# RJ45_Sheet.net
KiCad netlist of a schematic drawn in Altium Designer
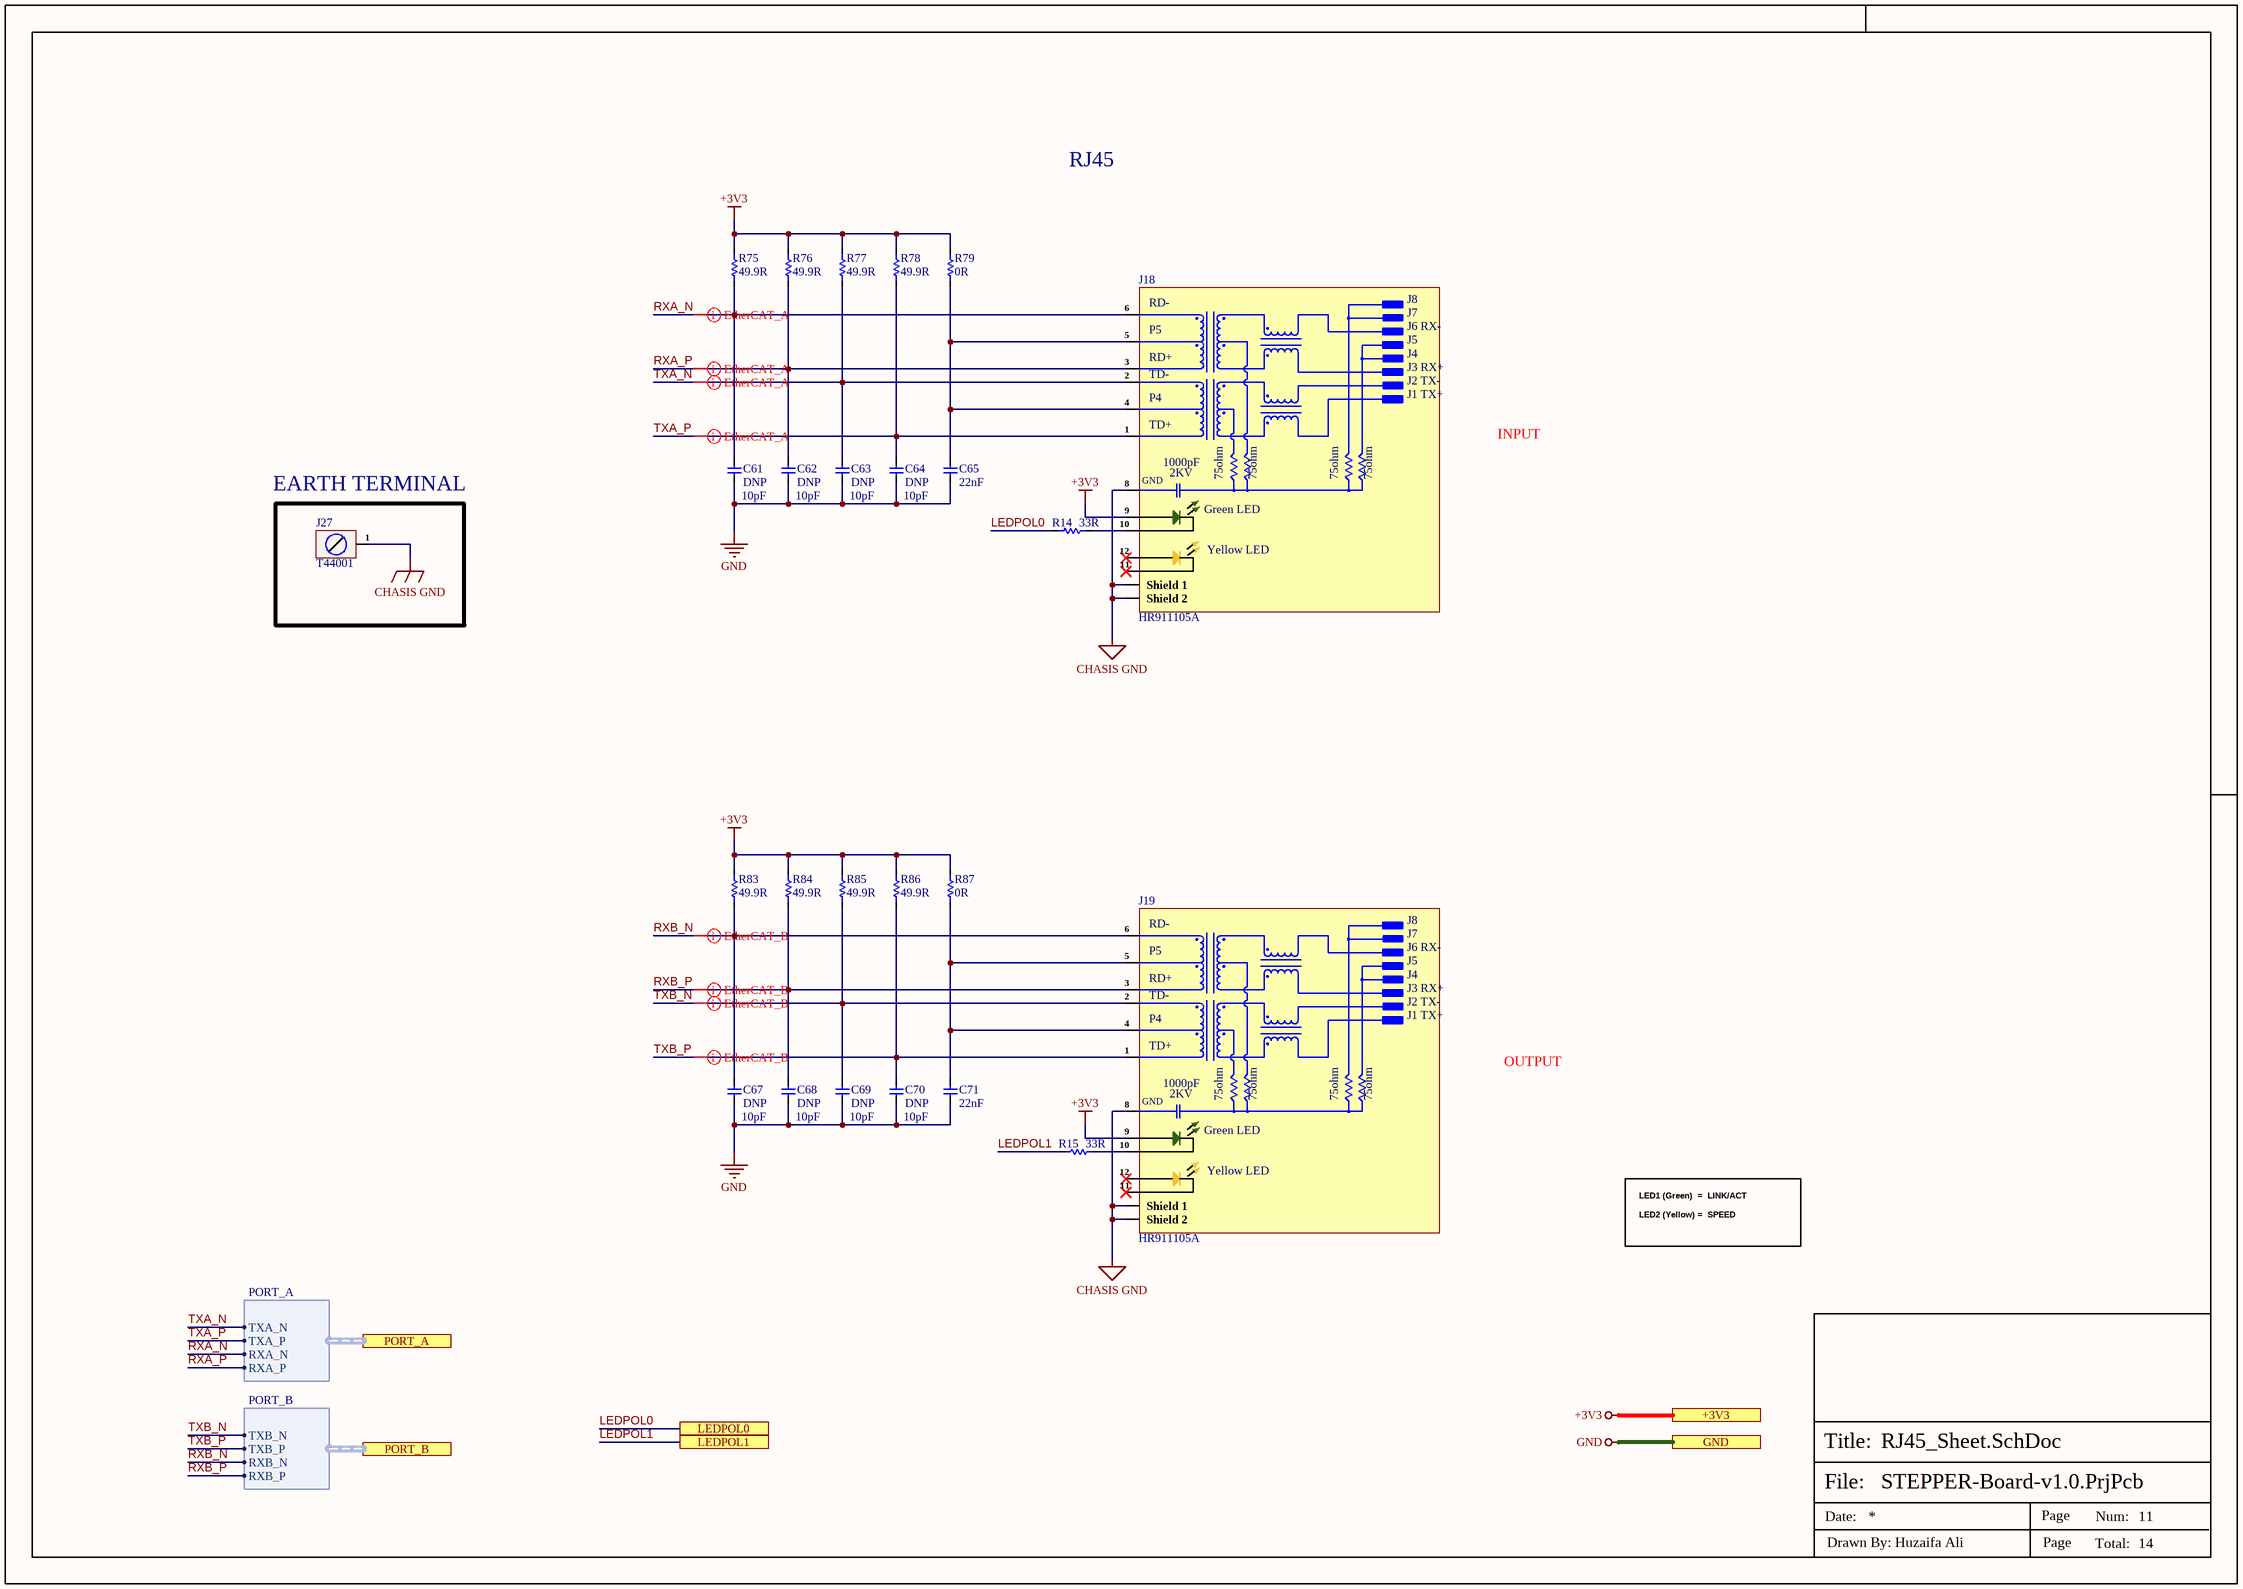
[diagram p0: RJ45_Sheet.SchDoc]

(export (version "E")
  (design (tool "Eeschema 10.0.6"))
  (components
    (comp (ref "C61")
      (value "DNP")
      (footprint "Cap-0402")
      (description "CAP CER 10PF 50V C0G/NP0 0402")
      (fields
        (field (name "MANUFACTURER") "Murata")
        (field (name "MANUFACTURER PART NUMBER") "GRM1555C1H100JA01D")
      )
      (libsource (lib "eSpark Libraries") (part "GRM1555C1H100JA01D"))
    )
    (comp (ref "C62")
      (value "DNP")
      (footprint "Cap-0402")
      (description "CAP CER 10PF 50V C0G/NP0 0402")
      (fields
        (field (name "MANUFACTURER") "Murata")
        (field (name "MANUFACTURER PART NUMBER") "GRM1555C1H100JA01D")
      )
      (libsource (lib "eSpark Libraries") (part "GRM1555C1H100JA01D"))
    )
    (comp (ref "C63")
      (value "DNP")
      (footprint "Cap-0402")
      (description "CAP CER 10PF 50V C0G/NP0 0402")
      (fields
        (field (name "MANUFACTURER") "Murata")
        (field (name "MANUFACTURER PART NUMBER") "GRM1555C1H100JA01D")
      )
      (libsource (lib "eSpark Libraries") (part "GRM1555C1H100JA01D"))
    )
    (comp (ref "C64")
      (value "DNP")
      (footprint "Cap-0402")
      (description "CAP CER 10PF 50V C0G/NP0 0402")
      (fields
        (field (name "MANUFACTURER") "Murata")
        (field (name "MANUFACTURER PART NUMBER") "GRM1555C1H100JA01D")
      )
      (libsource (lib "eSpark Libraries") (part "GRM1555C1H100JA01D"))
    )
    (comp (ref "C65")
      (value "22nF")
      (footprint "Cap-0402")
      (description "CAP CER 0.022UF 16V X7R 0402")
      (fields
        (field (name "MANUFACTURER") "Yageo")
        (field (name "MANUFACTURER PART NUMBER") "CC0402JRX7R7BB223")
      )
      (libsource (lib "eSpark Libraries") (part "CC0402JRX7R7BB223"))
    )
    (comp (ref "C67")
      (value "DNP")
      (footprint "Cap-0402")
      (description "CAP CER 10PF 50V C0G/NP0 0402")
      (fields
        (field (name "MANUFACTURER") "Murata")
        (field (name "MANUFACTURER PART NUMBER") "GRM1555C1H100JA01D")
      )
      (libsource (lib "eSpark Libraries") (part "GRM1555C1H100JA01D"))
    )
    (comp (ref "C68")
      (value "DNP")
      (footprint "Cap-0402")
      (description "CAP CER 10PF 50V C0G/NP0 0402")
      (fields
        (field (name "MANUFACTURER") "Murata")
        (field (name "MANUFACTURER PART NUMBER") "GRM1555C1H100JA01D")
      )
      (libsource (lib "eSpark Libraries") (part "GRM1555C1H100JA01D"))
    )
    (comp (ref "C69")
      (value "DNP")
      (footprint "Cap-0402")
      (description "CAP CER 10PF 50V C0G/NP0 0402")
      (fields
        (field (name "MANUFACTURER") "Murata")
        (field (name "MANUFACTURER PART NUMBER") "GRM1555C1H100JA01D")
      )
      (libsource (lib "eSpark Libraries") (part "GRM1555C1H100JA01D"))
    )
    (comp (ref "C70")
      (value "DNP")
      (footprint "Cap-0402")
      (description "CAP CER 10PF 50V C0G/NP0 0402")
      (fields
        (field (name "MANUFACTURER") "Murata")
        (field (name "MANUFACTURER PART NUMBER") "GRM1555C1H100JA01D")
      )
      (libsource (lib "eSpark Libraries") (part "GRM1555C1H100JA01D"))
    )
    (comp (ref "C71")
      (value "22nF")
      (footprint "Cap-0402")
      (description "CAP CER 0.022UF 16V X7R 0402")
      (fields
        (field (name "MANUFACTURER") "Yageo")
        (field (name "MANUFACTURER PART NUMBER") "CC0402JRX7R7BB223")
      )
      (libsource (lib "eSpark Libraries") (part "CC0402JRX7R7BB223"))
    )
    (comp (ref "J18")
      (value "HR911105A")
      (footprint "HR911105A")
      (description "RJ45 RJReceptacle 1 WithLED Plugin Ethernet Connectors/Modular Connectors (RJ45 RJ11) ROHS")
      (fields (field (name "MANUFACTURER") "HANRUN") (field (name "LCSC PART NUMBER") "C12074"))
      (libsource (lib "eSpark Libraries") (part "HR911105A"))
    )
    (comp (ref "J19")
      (value "HR911105A")
      (footprint "HR911105A")
      (description "RJ45 RJReceptacle 1 WithLED Plugin Ethernet Connectors/Modular Connectors (RJ45 RJ11) ROHS")
      (fields (field (name "MANUFACTURER") "HANRUN") (field (name "LCSC PART NUMBER") "C12074"))
      (libsource (lib "eSpark Libraries") (part "HR911105A"))
    )
    (comp (ref "J27")
      (value "T44001")
      (footprint "T44001")
      (description "M4 Plugin PCB Welding Terminal ROHS")
      (fields (field (name "MANUFACTURER") "XFCN"))
      (libsource (lib "eSpark Libraries") (part "T44001"))
    )
    (comp (ref "R14")
      (value "33R")
      (footprint "Res-0402")
      (description "RES 33 OHM 1% 1/16W 0402")
      (fields
        (field (name "MANUFACTURER") "Yageo")
        (field (name "MANUFACTURER PART NUMBER") "RC0402FR-0733RL")
      )
      (libsource (lib "eSpark Libraries") (part "RC0402FR-0733RL"))
    )
    (comp (ref "R15")
      (value "33R")
      (footprint "Res-0402")
      (description "RES 33 OHM 1% 1/16W 0402")
      (fields
        (field (name "MANUFACTURER") "Yageo")
        (field (name "MANUFACTURER PART NUMBER") "RC0402FR-0733RL")
      )
      (libsource (lib "eSpark Libraries") (part "RC0402FR-0733RL"))
    )
    (comp (ref "R75")
      (value "49.9R")
      (footprint "Res-0603")
      (description "RES 49.9 OHM 1% 1/10W 0603")
      (fields
        (field (name "MANUFACTURER") "Yageo")
        (field (name "MANUFACTURER PART NUMBER") "RC0603FR-0749R9L")
      )
      (libsource (lib "eSpark Libraries") (part "RC0603FR-0749R9L"))
    )
    (comp (ref "R76")
      (value "49.9R")
      (footprint "Res-0603")
      (description "RES 49.9 OHM 1% 1/10W 0603")
      (fields
        (field (name "MANUFACTURER") "Yageo")
        (field (name "MANUFACTURER PART NUMBER") "RC0603FR-0749R9L")
      )
      (libsource (lib "eSpark Libraries") (part "RC0603FR-0749R9L"))
    )
    (comp (ref "R77")
      (value "49.9R")
      (footprint "Res-0603")
      (description "RES 49.9 OHM 1% 1/10W 0603")
      (fields
        (field (name "MANUFACTURER") "Yageo")
        (field (name "MANUFACTURER PART NUMBER") "RC0603FR-0749R9L")
      )
      (libsource (lib "eSpark Libraries") (part "RC0603FR-0749R9L"))
    )
    (comp (ref "R78")
      (value "49.9R")
      (footprint "Res-0603")
      (description "RES 49.9 OHM 1% 1/10W 0603")
      (fields
        (field (name "MANUFACTURER") "Yageo")
        (field (name "MANUFACTURER PART NUMBER") "RC0603FR-0749R9L")
      )
      (libsource (lib "eSpark Libraries") (part "RC0603FR-0749R9L"))
    )
    (comp (ref "R79")
      (value "0R")
      (footprint "Res-0402")
      (description "RESISTOR 0402 JUMPER ZERO OHM")
      (fields
        (field (name "MANUFACTURER") "Yageo")
        (field (name "MANUFACTURER PART NUMBER") "AC0402FR-070RL")
      )
      (libsource (lib "eSpark Libraries") (part "AC0402FR-070RL"))
    )
    (comp (ref "R83")
      (value "49.9R")
      (footprint "Res-0603")
      (description "RES 49.9 OHM 1% 1/10W 0603")
      (fields
        (field (name "MANUFACTURER") "Yageo")
        (field (name "MANUFACTURER PART NUMBER") "RC0603FR-0749R9L")
      )
      (libsource (lib "eSpark Libraries") (part "RC0603FR-0749R9L"))
    )
    (comp (ref "R84")
      (value "49.9R")
      (footprint "Res-0603")
      (description "RES 49.9 OHM 1% 1/10W 0603")
      (fields
        (field (name "MANUFACTURER") "Yageo")
        (field (name "MANUFACTURER PART NUMBER") "RC0603FR-0749R9L")
      )
      (libsource (lib "eSpark Libraries") (part "RC0603FR-0749R9L"))
    )
    (comp (ref "R85")
      (value "49.9R")
      (footprint "Res-0603")
      (description "RES 49.9 OHM 1% 1/10W 0603")
      (fields
        (field (name "MANUFACTURER") "Yageo")
        (field (name "MANUFACTURER PART NUMBER") "RC0603FR-0749R9L")
      )
      (libsource (lib "eSpark Libraries") (part "RC0603FR-0749R9L"))
    )
    (comp (ref "R86")
      (value "49.9R")
      (footprint "Res-0603")
      (description "RES 49.9 OHM 1% 1/10W 0603")
      (fields
        (field (name "MANUFACTURER") "Yageo")
        (field (name "MANUFACTURER PART NUMBER") "RC0603FR-0749R9L")
      )
      (libsource (lib "eSpark Libraries") (part "RC0603FR-0749R9L"))
    )
    (comp (ref "R87")
      (value "0R")
      (footprint "Res-0402")
      (description "RESISTOR 0402 JUMPER ZERO OHM")
      (fields
        (field (name "MANUFACTURER") "Yageo")
        (field (name "MANUFACTURER PART NUMBER") "AC0402FR-070RL")
      )
      (libsource (lib "eSpark Libraries") (part "AC0402FR-070RL"))
    )
  )
  (nets
    (net (code "3") (name "+3V3") (class "Default")
      (node (ref "J18") (pin "9") (pinfunction "ANODE_9") (pintype "passive"))
      (node (ref "J19") (pin "9") (pinfunction "ANODE_9") (pintype "passive"))
      (node (ref "R75") (pin "2") (pinfunction "2_2") (pintype "passive"))
      (node (ref "R76") (pin "2") (pinfunction "2_2") (pintype "passive"))
      (node (ref "R77") (pin "2") (pinfunction "2_2") (pintype "passive"))
      (node (ref "R78") (pin "2") (pinfunction "2_2") (pintype "passive"))
      (node (ref "R79") (pin "2") (pinfunction "2_2") (pintype "passive"))
      (node (ref "R83") (pin "2") (pinfunction "2_2") (pintype "passive"))
      (node (ref "R84") (pin "2") (pinfunction "2_2") (pintype "passive"))
      (node (ref "R85") (pin "2") (pinfunction "2_2") (pintype "passive"))
      (node (ref "R86") (pin "2") (pinfunction "2_2") (pintype "passive"))
      (node (ref "R87") (pin "2") (pinfunction "2_2") (pintype "passive"))
    )
    (net (code "4") (name "/LEDPOL0") (class "Default")
      (node (ref "R14") (pin "1") (pinfunction "1_1") (pintype "passive"))
    )
    (net (code "5") (name "/LEDPOL1") (class "Default")
      (node (ref "R15") (pin "1") (pinfunction "1_1") (pintype "passive"))
    )
    (net (code "6") (name "/RXA_N") (class "Default")
      (node (ref "C61") (pin "2") (pinfunction "2_2") (pintype "passive"))
      (node (ref "J18") (pin "6") (pinfunction "RD-_6") (pintype "passive"))
      (node (ref "R75") (pin "1") (pinfunction "1_1") (pintype "passive"))
    )
    (net (code "7") (name "/RXA_P") (class "Default")
      (node (ref "C62") (pin "2") (pinfunction "2_2") (pintype "passive"))
      (node (ref "J18") (pin "3") (pinfunction "RD+_3") (pintype "passive"))
      (node (ref "R76") (pin "1") (pinfunction "1_1") (pintype "passive"))
    )
    (net (code "8") (name "/RXB_N") (class "Default")
      (node (ref "C67") (pin "2") (pinfunction "2_2") (pintype "passive"))
      (node (ref "J19") (pin "6") (pinfunction "RD-_6") (pintype "passive"))
      (node (ref "R83") (pin "1") (pinfunction "1_1") (pintype "passive"))
    )
    (net (code "9") (name "/RXB_P") (class "Default")
      (node (ref "C68") (pin "2") (pinfunction "2_2") (pintype "passive"))
      (node (ref "J19") (pin "3") (pinfunction "RD+_3") (pintype "passive"))
      (node (ref "R84") (pin "1") (pinfunction "1_1") (pintype "passive"))
    )
    (net (code "10") (name "/TXA_N") (class "Default")
      (node (ref "C63") (pin "2") (pinfunction "2_2") (pintype "passive"))
      (node (ref "J18") (pin "2") (pinfunction "TD-_2") (pintype "passive"))
      (node (ref "R77") (pin "1") (pinfunction "1_1") (pintype "passive"))
    )
    (net (code "11") (name "/TXA_P") (class "Default")
      (node (ref "C64") (pin "2") (pinfunction "2_2") (pintype "passive"))
      (node (ref "J18") (pin "1") (pinfunction "TD+_1") (pintype "passive"))
      (node (ref "R78") (pin "1") (pinfunction "1_1") (pintype "passive"))
    )
    (net (code "12") (name "/TXB_N") (class "Default")
      (node (ref "C69") (pin "2") (pinfunction "2_2") (pintype "passive"))
      (node (ref "J19") (pin "2") (pinfunction "TD-_2") (pintype "passive"))
      (node (ref "R85") (pin "1") (pinfunction "1_1") (pintype "passive"))
    )
    (net (code "13") (name "/TXB_P") (class "Default")
      (node (ref "C70") (pin "2") (pinfunction "2_2") (pintype "passive"))
      (node (ref "J19") (pin "1") (pinfunction "TD+_1") (pintype "passive"))
      (node (ref "R86") (pin "1") (pinfunction "1_1") (pintype "passive"))
    )
    (net (code "16") (name "CHASIS GND") (class "Default")
      (node (ref "J18") (pin "8") (pinfunction "GND_8") (pintype "power_in"))
      (node (ref "J18") (pin "Shield_1") (pinfunction "Shield_1_Shield_1") (pintype "passive"))
      (node (ref "J18") (pin "Shield_2") (pinfunction "Shield_2_Shield_2") (pintype "passive"))
      (node (ref "J19") (pin "8") (pinfunction "GND_8") (pintype "power_in"))
      (node (ref "J19") (pin "Shield_1") (pinfunction "Shield_1_Shield_1") (pintype "passive"))
      (node (ref "J19") (pin "Shield_2") (pinfunction "Shield_2_Shield_2") (pintype "passive"))
      (node (ref "J27") (pin "1") (pinfunction "1_1") (pintype "passive"))
    )
    (net (code "17") (name "GND") (class "Default")
      (node (ref "C61") (pin "1") (pinfunction "1_1") (pintype "passive"))
      (node (ref "C62") (pin "1") (pinfunction "1_1") (pintype "passive"))
      (node (ref "C63") (pin "1") (pinfunction "1_1") (pintype "passive"))
      (node (ref "C64") (pin "1") (pinfunction "1_1") (pintype "passive"))
      (node (ref "C65") (pin "1") (pinfunction "1_1") (pintype "passive"))
      (node (ref "C67") (pin "1") (pinfunction "1_1") (pintype "passive"))
      (node (ref "C68") (pin "1") (pinfunction "1_1") (pintype "passive"))
      (node (ref "C69") (pin "1") (pinfunction "1_1") (pintype "passive"))
      (node (ref "C70") (pin "1") (pinfunction "1_1") (pintype "passive"))
      (node (ref "C71") (pin "1") (pinfunction "1_1") (pintype "passive"))
    )
    (net (code "18") (name "Net-(J18-CATHODE-Pad10)") (class "Default")
      (node (ref "J18") (pin "10") (pinfunction "CATHODE_10") (pintype "passive"))
      (node (ref "R14") (pin "2") (pinfunction "2_2") (pintype "passive"))
    )
    (net (code "19") (name "Net-(J18-P4)") (class "Default")
      (node (ref "C65") (pin "2") (pinfunction "2_2") (pintype "passive"))
      (node (ref "J18") (pin "4") (pinfunction "P4_4") (pintype "passive"))
      (node (ref "J18") (pin "5") (pinfunction "P5_5") (pintype "passive"))
      (node (ref "R79") (pin "1") (pinfunction "1_1") (pintype "passive"))
    )
    (net (code "20") (name "Net-(J19-CATHODE-Pad10)") (class "Default")
      (node (ref "J19") (pin "10") (pinfunction "CATHODE_10") (pintype "passive"))
      (node (ref "R15") (pin "2") (pinfunction "2_2") (pintype "passive"))
    )
    (net (code "21") (name "Net-(J19-P4)") (class "Default")
      (node (ref "C71") (pin "2") (pinfunction "2_2") (pintype "passive"))
      (node (ref "J19") (pin "4") (pinfunction "P4_4") (pintype "passive"))
      (node (ref "J19") (pin "5") (pinfunction "P5_5") (pintype "passive"))
      (node (ref "R87") (pin "1") (pinfunction "1_1") (pintype "passive"))
    )
    (net (code "22") (name "unconnected-(J18-ANODE-Pad12)") (class "Default")
      (node (ref "J18") (pin "12") (pinfunction "ANODE_12") (pintype "passive+no_connect"))
    )
    (net (code "23") (name "unconnected-(J18-CATHODE-Pad11)") (class "Default")
      (node (ref "J18") (pin "11") (pinfunction "CATHODE_11") (pintype "passive+no_connect"))
    )
    (net (code "24") (name "unconnected-(J19-ANODE-Pad12)") (class "Default")
      (node (ref "J19") (pin "12") (pinfunction "ANODE_12") (pintype "passive+no_connect"))
    )
    (net (code "25") (name "unconnected-(J19-CATHODE-Pad11)") (class "Default")
      (node (ref "J19") (pin "11") (pinfunction "CATHODE_11") (pintype "passive+no_connect"))
    )
  )
)
